# BlinkerAC.net
KiCad netlist of a schematic drawn in Altium Designer
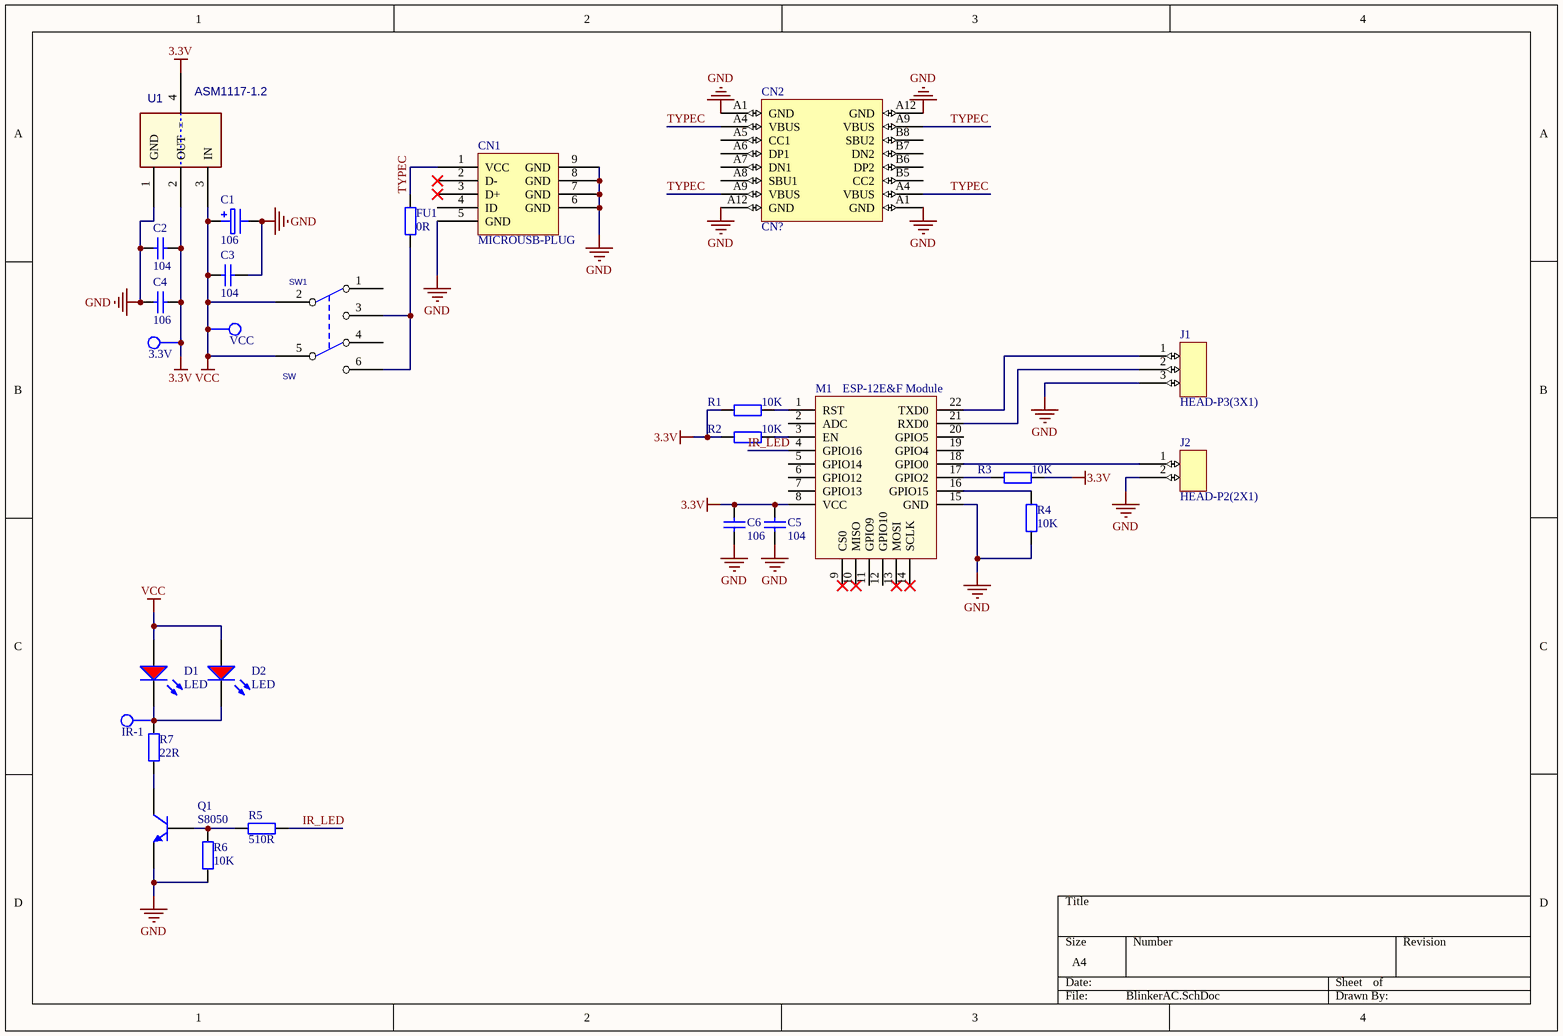
[diagram p0: BlinkerAC.SchDoc]

(export (version "E")
  (design (tool "Eeschema 10.0.6"))
  (components
    (comp (ref "3.3V") (value "TP") (footprint "TEST 1.2") (libsource (lib "MarkX") (part "TP")))
    (comp (ref "C1")
      (value "106")
      (footprint "CASE-A_3216")
      (description "POLAR")
      (libsource (lib "MarkX") (part "Capacity_Murphy"))
    )
    (comp (ref "C2")
      (value "104")
      (footprint "0603_C")
      (description "ceramic")
      (libsource (lib "MarkX") (part "Capacity_ceramic_Murphy"))
    )
    (comp (ref "C3")
      (value "104")
      (footprint "0603_C")
      (description "ceramic")
      (libsource (lib "MarkX") (part "Capacity_ceramic_Murphy"))
    )
    (comp (ref "C4")
      (value "106")
      (footprint "0805_C")
      (description "ceramic")
      (libsource (lib "MarkX") (part "Capacity_ceramic_Murphy"))
    )
    (comp (ref "C5")
      (value "104")
      (footprint "0402_C")
      (description "ceramic")
      (libsource (lib "MarkX") (part "Capacity_ceramic_Murphy"))
    )
    (comp (ref "C6")
      (value "106")
      (footprint "0805_C")
      (description "ceramic")
      (libsource (lib "MarkX") (part "Capacity_ceramic_Murphy"))
    )
    (comp (ref "CN1")
      (value "MICROUSB-PLUG")
      (footprint "Mini_USB")
      (libsource (lib "MarkX") (part "MICROUSB-PLUG"))
    )
    (comp (ref "CN2")
      (value "CN?")
      (footprint "type-c")
      (description "TYPEC16-PLUG")
      (libsource (lib "MarkX") (part "TYPEC16-PLUG"))
    )
    (comp (ref "D1")
      (value "LED")
      (footprint "LED 5MM-R")
      (description "LED（Red）")
      (libsource (lib "MarkX") (part "LED_Murphy"))
    )
    (comp (ref "D2")
      (value "LED")
      (footprint "LED 5MM-R")
      (description "LED（Red）")
      (libsource (lib "MarkX") (part "LED_Murphy"))
    )
    (comp (ref "FU1")
      (value "0R")
      (footprint "0805_R")
      (description "电阻")
      (libsource (lib "") (part "Resistor_Murphy_1"))
    )
    (comp (ref "IR-1") (value "TP") (footprint "TEST 1.2") (libsource (lib "MarkX") (part "TP")))
    (comp (ref "J1")
      (value "HEAD-P3(3X1)")
      (footprint "2.54mm PIN3 (3X1)")
      (libsource (lib "MarkX") (part "HEAD-P3(3X1)"))
    )
    (comp (ref "J2")
      (value "HEAD-P2(2X1)")
      (footprint "2.54mm PIN2 (2X1)")
      (libsource (lib "MarkX") (part "HEAD-P2(2X1)"))
    )
    (comp (ref "M1")
      (value "ESP-12E&F Module")
      (footprint "ESP-12E&F Module")
      (libsource (lib "MarkX") (part "ESP-12E&F Module"))
    )
    (comp (ref "Q1")
      (value "S8050")
      (footprint "SOT-23(SOT-23-3)")
      (description "NPN Transistor")
      (libsource (lib "MarkX") (part "S8050"))
    )
    (comp (ref "R1")
      (value "10K")
      (footprint "0402_R")
      (description "电阻")
      (libsource (lib "MarkX") (part "Resistor_Murphy"))
    )
    (comp (ref "R2")
      (value "10K")
      (footprint "0402_R")
      (description "电阻")
      (libsource (lib "MarkX") (part "Resistor_Murphy"))
    )
    (comp (ref "R3")
      (value "10K")
      (footprint "0402_R")
      (description "电阻")
      (libsource (lib "MarkX") (part "Resistor_Murphy"))
    )
    (comp (ref "R4")
      (value "10K")
      (footprint "0402_R")
      (description "电阻")
      (libsource (lib "") (part "Resistor_Murphy_2"))
    )
    (comp (ref "R5")
      (value "510R")
      (footprint "0402_R")
      (description "电阻")
      (libsource (lib "MarkX") (part "Resistor_Murphy"))
    )
    (comp (ref "R6")
      (value "10K")
      (footprint "0402_R")
      (description "电阻")
      (libsource (lib "") (part "Resistor_Murphy_1"))
    )
    (comp (ref "R7")
      (value "22R")
      (footprint "0402_R")
      (description "电阻")
      (libsource (lib "") (part "Resistor_Murphy_1"))
    )
    (comp (ref "SW1") (value "SW") (libsource (lib "MarkX") (part "SW KEY-DPDT")))
    (comp (ref "U1")
      (value "ASM1117-1.2")
      (footprint "SOT223")
      (description "LDO")
      (libsource (lib "MarkX") (part "ASM1117-1.2"))
    )
    (comp (ref "VCC") (value "TP") (footprint "TEST 1.2") (libsource (lib "MarkX") (part "TP")))
  )
  (nets
    (net (code "1") (name "/IR_LED") (class "Default")
      (node (ref "M1") (pin "4") (pinfunction "GPIO16_4") (pintype "passive"))
      (node (ref "R5") (pin "1") (pinfunction "1_1") (pintype "passive"))
    )
    (net (code "2") (name "/TYPEC") (class "Default")
      (node (ref "CN1") (pin "1") (pinfunction "VCC_1") (pintype "passive"))
      (node (ref "CN2") (pin "A4") (pinfunction "VBUS_A4") (pintype "bidirectional"))
      (node (ref "CN2") (pin "A9") (pinfunction "VBUS_A9") (pintype "bidirectional"))
      (node (ref "FU1") (pin "1") (pinfunction "1_1") (pintype "passive"))
    )
    (net (code "3") (name "3.3V") (class "Default")
      (node (ref "3.3V") (pin "1") (pinfunction "TP_1") (pintype "passive"))
      (node (ref "C2") (pin "1") (pinfunction "1_1") (pintype "passive"))
      (node (ref "C4") (pin "1") (pinfunction "1_1") (pintype "passive"))
      (node (ref "C5") (pin "2") (pinfunction "2_2") (pintype "passive"))
      (node (ref "C6") (pin "1") (pinfunction "1_1") (pintype "passive"))
      (node (ref "M1") (pin "8") (pinfunction "VCC_8") (pintype "passive"))
      (node (ref "R1") (pin "2") (pinfunction "2_2") (pintype "passive"))
      (node (ref "R2") (pin "2") (pinfunction "2_2") (pintype "passive"))
      (node (ref "R3") (pin "1") (pinfunction "1_1") (pintype "passive"))
      (node (ref "U1") (pin "2") (pinfunction "OUT_2") (pintype "passive"))
      (node (ref "U1") (pin "4") (pinfunction "=_4") (pintype "passive"))
    )
    (net (code "4") (name "GND") (class "Default")
      (node (ref "C1") (pin "2") (pinfunction "2_2") (pintype "passive"))
      (node (ref "C2") (pin "2") (pinfunction "2_2") (pintype "passive"))
      (node (ref "C3") (pin "1") (pinfunction "1_1") (pintype "passive"))
      (node (ref "C4") (pin "2") (pinfunction "2_2") (pintype "passive"))
      (node (ref "C5") (pin "1") (pinfunction "1_1") (pintype "passive"))
      (node (ref "C6") (pin "2") (pinfunction "2_2") (pintype "passive"))
      (node (ref "CN1") (pin "5") (pinfunction "GND_5") (pintype "passive"))
      (node (ref "CN1") (pin "6") (pinfunction "GND_6") (pintype "passive"))
      (node (ref "CN1") (pin "7") (pinfunction "GND_7") (pintype "passive"))
      (node (ref "CN1") (pin "8") (pinfunction "GND_8") (pintype "passive"))
      (node (ref "CN1") (pin "9") (pinfunction "GND_9") (pintype "passive"))
      (node (ref "CN2") (pin "A1") (pinfunction "GND_A1") (pintype "bidirectional"))
      (node (ref "CN2") (pin "A12") (pinfunction "GND_A12") (pintype "bidirectional"))
      (node (ref "J1") (pin "3") (pintype "bidirectional"))
      (node (ref "J2") (pin "2") (pintype "bidirectional"))
      (node (ref "M1") (pin "15") (pinfunction "GND_15") (pintype "passive"))
      (node (ref "Q1") (pin "2") (pinfunction "E_2") (pintype "passive"))
      (node (ref "R4") (pin "1") (pinfunction "1_1") (pintype "passive"))
      (node (ref "R6") (pin "2") (pinfunction "2_2") (pintype "passive"))
      (node (ref "U1") (pin "1") (pinfunction "GND_1") (pintype "passive"))
    )
    (net (code "5") (name "Net-(IR-1-TP)") (class "Default")
      (node (ref "D1") (pin "K") (pinfunction "K_K") (pintype "passive"))
      (node (ref "D2") (pin "K") (pinfunction "K_K") (pintype "passive"))
      (node (ref "IR-1") (pin "1") (pinfunction "TP_1") (pintype "passive"))
      (node (ref "R7") (pin "1") (pinfunction "1_1") (pintype "passive"))
    )
    (net (code "6") (name "Net-(M1-EN)") (class "Default")
      (node (ref "M1") (pin "3") (pinfunction "EN_3") (pintype "passive"))
      (node (ref "R2") (pin "1") (pinfunction "1_1") (pintype "passive"))
    )
    (net (code "7") (name "Net-(M1-GPIO0)") (class "Default")
      (node (ref "J2") (pin "1") (pintype "bidirectional"))
      (node (ref "M1") (pin "18") (pinfunction "GPIO0_18") (pintype "passive"))
    )
    (net (code "8") (name "Net-(M1-GPIO2)") (class "Default")
      (node (ref "M1") (pin "17") (pinfunction "GPIO2_17") (pintype "passive"))
      (node (ref "R3") (pin "2") (pinfunction "2_2") (pintype "passive"))
    )
    (net (code "9") (name "Net-(M1-GPIO15)") (class "Default")
      (node (ref "M1") (pin "16") (pinfunction "GPIO15_16") (pintype "passive"))
      (node (ref "R4") (pin "2") (pinfunction "2_2") (pintype "passive"))
    )
    (net (code "10") (name "Net-(M1-RST)") (class "Default")
      (node (ref "M1") (pin "1") (pinfunction "RST_1") (pintype "passive"))
      (node (ref "R1") (pin "1") (pinfunction "1_1") (pintype "passive"))
    )
    (net (code "11") (name "Net-(M1-RXD0)") (class "Default")
      (node (ref "J1") (pin "2") (pintype "bidirectional"))
      (node (ref "M1") (pin "21") (pinfunction "RXD0_21") (pintype "passive"))
    )
    (net (code "12") (name "Net-(M1-TXD0)") (class "Default")
      (node (ref "J1") (pin "1") (pintype "bidirectional"))
      (node (ref "M1") (pin "22") (pinfunction "TXD0_22") (pintype "passive"))
    )
    (net (code "13") (name "Net-(Q1-B)") (class "Default")
      (node (ref "Q1") (pin "1") (pinfunction "B_1") (pintype "passive"))
      (node (ref "R5") (pin "2") (pinfunction "2_2") (pintype "passive"))
      (node (ref "R6") (pin "1") (pinfunction "1_1") (pintype "passive"))
    )
    (net (code "14") (name "Net-(Q1-C)") (class "Default")
      (node (ref "Q1") (pin "3") (pinfunction "C_3") (pintype "passive"))
      (node (ref "R7") (pin "2") (pinfunction "2_2") (pintype "passive"))
    )
    (net (code "15") (name "Net-(SW1-NO1)") (class "Default")
      (node (ref "FU1") (pin "2") (pinfunction "2_2") (pintype "passive"))
      (node (ref "SW1") (pin "3") (pinfunction "NO1_3") (pintype "passive"))
      (node (ref "SW1") (pin "6") (pinfunction "NO2_6") (pintype "passive"))
    )
    (net (code "16") (name "VCC") (class "Default")
      (node (ref "C1") (pin "1") (pinfunction "1_1") (pintype "passive"))
      (node (ref "C3") (pin "2") (pinfunction "2_2") (pintype "passive"))
      (node (ref "D1") (pin "A") (pinfunction "A_A") (pintype "passive"))
      (node (ref "D2") (pin "A") (pinfunction "A_A") (pintype "passive"))
      (node (ref "SW1") (pin "2") (pinfunction "COMMON1_2") (pintype "passive"))
      (node (ref "SW1") (pin "5") (pinfunction "COMMON2_5") (pintype "passive"))
      (node (ref "U1") (pin "3") (pinfunction "IN_3") (pintype "passive"))
      (node (ref "VCC") (pin "1") (pinfunction "TP_1") (pintype "passive"))
    )
    (net (code "17") (name "unconnected-(CN1-D+-Pad3)") (class "Default")
      (node (ref "CN1") (pin "3") (pinfunction "D+_3") (pintype "passive+no_connect"))
    )
    (net (code "18") (name "unconnected-(CN1-D--Pad2)") (class "Default")
      (node (ref "CN1") (pin "2") (pinfunction "D-_2") (pintype "passive+no_connect"))
    )
    (net (code "19") (name "unconnected-(CN1-ID-Pad4)") (class "Default")
      (node (ref "CN1") (pin "4") (pinfunction "ID_4") (pintype "passive"))
    )
    (net (code "20") (name "unconnected-(CN2-CC1-PadA5)") (class "Default")
      (node (ref "CN2") (pin "A5") (pinfunction "CC1_A5") (pintype "bidirectional"))
    )
    (net (code "21") (name "unconnected-(CN2-CC2-PadB5)") (class "Default")
      (node (ref "CN2") (pin "B5") (pinfunction "CC2_B5") (pintype "bidirectional"))
    )
    (net (code "22") (name "unconnected-(CN2-DN1-PadA7)") (class "Default")
      (node (ref "CN2") (pin "A7") (pinfunction "DN1_A7") (pintype "bidirectional"))
    )
    (net (code "23") (name "unconnected-(CN2-DN2-PadB7)") (class "Default")
      (node (ref "CN2") (pin "B7") (pinfunction "DN2_B7") (pintype "bidirectional"))
    )
    (net (code "24") (name "unconnected-(CN2-DP1-PadA6)") (class "Default")
      (node (ref "CN2") (pin "A6") (pinfunction "DP1_A6") (pintype "bidirectional"))
    )
    (net (code "25") (name "unconnected-(CN2-DP2-PadB6)") (class "Default")
      (node (ref "CN2") (pin "B6") (pinfunction "DP2_B6") (pintype "bidirectional"))
    )
    (net (code "26") (name "unconnected-(CN2-SBU1-PadA8)") (class "Default")
      (node (ref "CN2") (pin "A8") (pinfunction "SBU1_A8") (pintype "bidirectional"))
    )
    (net (code "27") (name "unconnected-(CN2-SBU2-PadB8)") (class "Default")
      (node (ref "CN2") (pin "B8") (pinfunction "SBU2_B8") (pintype "bidirectional"))
    )
    (net (code "28") (name "unconnected-(M1-ADC-Pad2)") (class "Default")
      (node (ref "M1") (pin "2") (pinfunction "ADC_2") (pintype "passive"))
    )
    (net (code "29") (name "unconnected-(M1-CS0-Pad9)") (class "Default")
      (node (ref "M1") (pin "9") (pinfunction "CS0_9") (pintype "passive+no_connect"))
    )
    (net (code "30") (name "unconnected-(M1-GPIO4-Pad19)") (class "Default")
      (node (ref "M1") (pin "19") (pinfunction "GPIO4_19") (pintype "passive"))
    )
    (net (code "31") (name "unconnected-(M1-GPIO5-Pad20)") (class "Default")
      (node (ref "M1") (pin "20") (pinfunction "GPIO5_20") (pintype "passive"))
    )
    (net (code "32") (name "unconnected-(M1-GPIO9-Pad11)") (class "Default")
      (node (ref "M1") (pin "11") (pinfunction "GPIO9_11") (pintype "passive"))
    )
    (net (code "33") (name "unconnected-(M1-GPIO10-Pad12)") (class "Default")
      (node (ref "M1") (pin "12") (pinfunction "GPIO10_12") (pintype "passive"))
    )
    (net (code "34") (name "unconnected-(M1-GPIO12-Pad6)") (class "Default")
      (node (ref "M1") (pin "6") (pinfunction "GPIO12_6") (pintype "passive"))
    )
    (net (code "35") (name "unconnected-(M1-GPIO13-Pad7)") (class "Default")
      (node (ref "M1") (pin "7") (pinfunction "GPIO13_7") (pintype "passive"))
    )
    (net (code "36") (name "unconnected-(M1-GPIO14-Pad5)") (class "Default")
      (node (ref "M1") (pin "5") (pinfunction "GPIO14_5") (pintype "passive"))
    )
    (net (code "37") (name "unconnected-(M1-MISO-Pad10)") (class "Default")
      (node (ref "M1") (pin "10") (pinfunction "MISO_10") (pintype "passive+no_connect"))
    )
    (net (code "38") (name "unconnected-(M1-MOSI-Pad13)") (class "Default")
      (node (ref "M1") (pin "13") (pinfunction "MOSI_13") (pintype "passive+no_connect"))
    )
    (net (code "39") (name "unconnected-(M1-SCLK-Pad14)") (class "Default")
      (node (ref "M1") (pin "14") (pinfunction "SCLK_14") (pintype "passive+no_connect"))
    )
    (net (code "40") (name "unconnected-(SW1-NC1-Pad1)") (class "Default")
      (node (ref "SW1") (pin "1") (pinfunction "NC1_1") (pintype "passive"))
    )
    (net (code "41") (name "unconnected-(SW1-NC2-Pad4)") (class "Default")
      (node (ref "SW1") (pin "4") (pinfunction "NC2_4") (pintype "passive"))
    )
  )
)
